# DRV8825-isolated.net
KiCad netlist of a schematic drawn in EAGLE
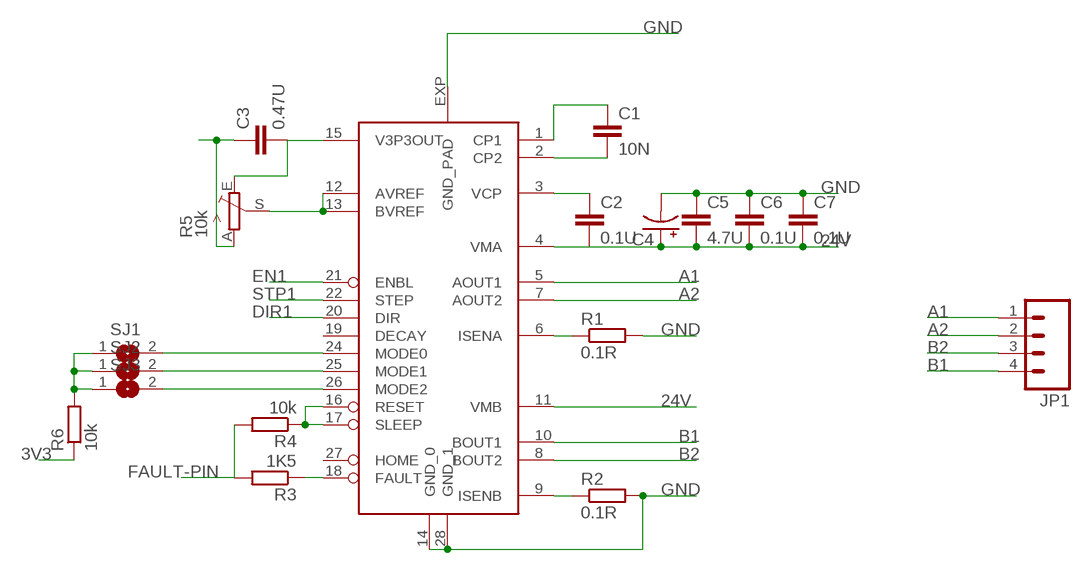
[diagram p0: schematic, sheet 1]

(export (version "E")
  (design (tool "Eeschema 10.0.6"))
  (components
    (comp (ref "C1")
      (value "10N")
      (footprint "eagle-import:1206")
      (libsource (lib "eagle-import") (part "CAP1206"))
    )
    (comp (ref "C2")
      (value "0.1U")
      (footprint "eagle-import:1206")
      (libsource (lib "eagle-import") (part "CAP1206"))
    )
    (comp (ref "C3")
      (value "0.47U")
      (footprint "eagle-import:1206")
      (libsource (lib "eagle-import") (part "CAP1206"))
    )
    (comp (ref "C4")
      (value "CPOL-USE2.5-7")
      (footprint "eagle-import:E2,5-7")
      (libsource (lib "eagle-import") (part "CPOL-USE2.5-7"))
    )
    (comp (ref "C5")
      (value "4.7U")
      (footprint "eagle-import:1206")
      (libsource (lib "eagle-import") (part "CAP1206"))
    )
    (comp (ref "C6")
      (value "0.1U")
      (footprint "eagle-import:1206")
      (libsource (lib "eagle-import") (part "CAP1206"))
    )
    (comp (ref "C7")
      (value "0.1U")
      (footprint "eagle-import:1206")
      (libsource (lib "eagle-import") (part "CAP1206"))
    )
    (comp (ref "JP1")
      (value "M04SCREW")
      (footprint "eagle-import:SCREWTERMINAL-3.5MM-4")
      (libsource (lib "eagle-import") (part "M04SCREW"))
    )
    (comp (ref "R1")
      (value "0.1R")
      (footprint "eagle-import:R1206")
      (libsource (lib "eagle-import") (part "R-EU_R1206"))
    )
    (comp (ref "R2")
      (value "0.1R")
      (footprint "eagle-import:R1206")
      (libsource (lib "eagle-import") (part "R-EU_R1206"))
    )
    (comp (ref "R3")
      (value "1K5")
      (footprint "eagle-import:M1206")
      (libsource (lib "eagle-import") (part "R-EU_M1206"))
    )
    (comp (ref "R4")
      (value "10k")
      (footprint "eagle-import:M1206")
      (libsource (lib "eagle-import") (part "R-EU_M1206"))
    )
    (comp (ref "R5")
      (value "10k")
      (footprint "eagle-import:S64W")
      (libsource (lib "eagle-import") (part "TRIM_EU-S64W"))
    )
    (comp (ref "R6")
      (value "10k")
      (footprint "eagle-import:R1206")
      (libsource (lib "eagle-import") (part "R-EU_R1206"))
    )
    (comp (ref "SJ1") (value "SJ") (footprint "eagle-import:SJ") (libsource (lib "eagle-import") (part "SJ")))
    (comp (ref "SJ2") (value "SJ") (footprint "eagle-import:SJ") (libsource (lib "eagle-import") (part "SJ")))
    (comp (ref "SJ3") (value "SJ") (footprint "eagle-import:SJ") (libsource (lib "eagle-import") (part "SJ")))
    (comp (ref "U$1")
      (value "DRV8825PWP")
      (footprint "eagle-import:TSSOP-28")
      (libsource (lib "eagle-import") (part "DRV8825PWP"))
    )
  )
  (nets
    (net (code "1") (name "/3V3") (class "Default")
      (node (ref "R6") (pin "1") (pinfunction "1_1") (pintype "passive"))
    )
    (net (code "2") (name "/24V") (class "Default")
      (node (ref "C2") (pin "2") (pinfunction "2_2") (pintype "passive"))
      (node (ref "C4") (pin "+") (pinfunction "+_+") (pintype "passive"))
      (node (ref "C5") (pin "2") (pinfunction "2_2") (pintype "passive"))
      (node (ref "C6") (pin "2") (pinfunction "2_2") (pintype "passive"))
      (node (ref "C7") (pin "2") (pinfunction "2_2") (pintype "passive"))
      (node (ref "U$1") (pin "11") (pinfunction "VMB_11") (pintype "power_in"))
      (node (ref "U$1") (pin "4") (pinfunction "VMA_4") (pintype "power_in"))
    )
    (net (code "3") (name "/A1") (class "Default")
      (node (ref "JP1") (pin "1") (pinfunction "1_1") (pintype "passive"))
      (node (ref "U$1") (pin "5") (pinfunction "AOUT1_5") (pintype "output"))
    )
    (net (code "4") (name "/A2") (class "Default")
      (node (ref "JP1") (pin "2") (pinfunction "2_2") (pintype "passive"))
      (node (ref "U$1") (pin "7") (pinfunction "AOUT2_7") (pintype "output"))
    )
    (net (code "5") (name "/B1") (class "Default")
      (node (ref "JP1") (pin "4") (pinfunction "4_4") (pintype "passive"))
      (node (ref "U$1") (pin "10") (pinfunction "BOUT1_10") (pintype "output"))
    )
    (net (code "6") (name "/B2") (class "Default")
      (node (ref "JP1") (pin "3") (pinfunction "3_3") (pintype "passive"))
      (node (ref "U$1") (pin "8") (pinfunction "BOUT2_8") (pintype "output"))
    )
    (net (code "7") (name "/DIR1") (class "Default")
      (node (ref "U$1") (pin "20") (pinfunction "DIR_20") (pintype "input"))
    )
    (net (code "8") (name "/EN1") (class "Default")
      (node (ref "U$1") (pin "21") (pinfunction "ENBL_21") (pintype "input"))
    )
    (net (code "9") (name "/FAULT-PIN") (class "Default")
      (node (ref "R3") (pin "2") (pinfunction "2_2") (pintype "passive"))
      (node (ref "R4") (pin "2") (pinfunction "2_2") (pintype "passive"))
    )
    (net (code "10") (name "/GND") (class "Default")
      (node (ref "C3") (pin "1") (pinfunction "1_1") (pintype "passive"))
      (node (ref "C4") (pin "-") (pinfunction "-_-") (pintype "passive"))
      (node (ref "C5") (pin "1") (pinfunction "1_1") (pintype "passive"))
      (node (ref "C6") (pin "1") (pinfunction "1_1") (pintype "passive"))
      (node (ref "C7") (pin "1") (pinfunction "1_1") (pintype "passive"))
      (node (ref "R1") (pin "2") (pinfunction "2_2") (pintype "passive"))
      (node (ref "R2") (pin "2") (pinfunction "2_2") (pintype "passive"))
      (node (ref "R5") (pin "A") (pinfunction "A_A") (pintype "passive"))
      (node (ref "U$1") (pin "14") (pinfunction "GND_0_14") (pintype "power_in"))
      (node (ref "U$1") (pin "28") (pinfunction "GND_1_28") (pintype "power_in"))
      (node (ref "U$1") (pin "EXP") (pinfunction "GND_PAD_EXP") (pintype "power_in"))
    )
    (net (code "11") (name "/MSPULLUP") (class "Default")
      (node (ref "R6") (pin "2") (pinfunction "2_2") (pintype "passive"))
      (node (ref "SJ1") (pin "1") (pinfunction "1_1") (pintype "passive"))
      (node (ref "SJ1") (pin "2") (pinfunction "2_2") (pintype "passive"))
      (node (ref "SJ2") (pin "1") (pinfunction "1_1") (pintype "passive"))
      (node (ref "SJ2") (pin "2") (pinfunction "2_2") (pintype "passive"))
      (node (ref "SJ3") (pin "1") (pinfunction "1_1") (pintype "passive"))
      (node (ref "SJ3") (pin "2") (pinfunction "2_2") (pintype "passive"))
      (node (ref "U$1") (pin "24") (pinfunction "MODE0_24") (pintype "input"))
      (node (ref "U$1") (pin "25") (pinfunction "MODE1_25") (pintype "input"))
      (node (ref "U$1") (pin "26") (pinfunction "MODE2_26") (pintype "input"))
    )
    (net (code "12") (name "/STP1") (class "Default")
      (node (ref "U$1") (pin "22") (pinfunction "STEP_22") (pintype "input"))
    )
    (net (code "13") (name "Net-(U$1-AVREF)") (class "Default")
      (node (ref "R5") (pin "S") (pinfunction "S_S") (pintype "passive"))
      (node (ref "U$1") (pin "12") (pinfunction "AVREF_12") (pintype "input"))
      (node (ref "U$1") (pin "13") (pinfunction "BVREF_13") (pintype "input"))
    )
    (net (code "14") (name "Net-(U$1-CP1)") (class "Default")
      (node (ref "C1") (pin "1") (pinfunction "1_1") (pintype "passive"))
      (node (ref "U$1") (pin "1") (pinfunction "CP1_1") (pintype "bidirectional"))
    )
    (net (code "15") (name "Net-(U$1-CP2)") (class "Default")
      (node (ref "C1") (pin "2") (pinfunction "2_2") (pintype "passive"))
      (node (ref "U$1") (pin "2") (pinfunction "CP2_2") (pintype "bidirectional"))
    )
    (net (code "16") (name "Net-(U$1-FAULT)") (class "Default")
      (node (ref "R3") (pin "1") (pinfunction "1_1") (pintype "passive"))
      (node (ref "U$1") (pin "18") (pinfunction "FAULT_18") (pintype "output"))
    )
    (net (code "17") (name "Net-(U$1-ISENA)") (class "Default")
      (node (ref "R1") (pin "1") (pinfunction "1_1") (pintype "passive"))
      (node (ref "U$1") (pin "6") (pinfunction "ISENA_6") (pintype "output"))
    )
    (net (code "18") (name "Net-(U$1-ISENB)") (class "Default")
      (node (ref "R2") (pin "1") (pinfunction "1_1") (pintype "passive"))
      (node (ref "U$1") (pin "9") (pinfunction "ISENB_9") (pintype "output"))
    )
    (net (code "19") (name "Net-(U$1-RESET)") (class "Default")
      (node (ref "R4") (pin "1") (pinfunction "1_1") (pintype "passive"))
      (node (ref "U$1") (pin "16") (pinfunction "RESET_16") (pintype "input"))
      (node (ref "U$1") (pin "17") (pinfunction "SLEEP_17") (pintype "input"))
    )
    (net (code "20") (name "Net-(U$1-V3P3OUT)") (class "Default")
      (node (ref "C3") (pin "2") (pinfunction "2_2") (pintype "passive"))
      (node (ref "R5") (pin "E") (pinfunction "E_E") (pintype "passive"))
      (node (ref "U$1") (pin "15") (pinfunction "V3P3OUT_15") (pintype "output"))
    )
    (net (code "21") (name "Net-(U$1-VCP)") (class "Default")
      (node (ref "C2") (pin "1") (pinfunction "1_1") (pintype "passive"))
      (node (ref "U$1") (pin "3") (pinfunction "VCP_3") (pintype "bidirectional"))
    )
    (net (code "22") (name "unconnected-(U$1-DECAY-Pad19)") (class "Default")
      (node (ref "U$1") (pin "19") (pinfunction "DECAY_19") (pintype "input"))
    )
    (net (code "23") (name "unconnected-(U$1-HOME-Pad27)") (class "Default")
      (node (ref "U$1") (pin "27") (pinfunction "HOME_27") (pintype "output"))
    )
  )
)
